# interface.net
KiCad netlist of a schematic drawn in Altium Designer
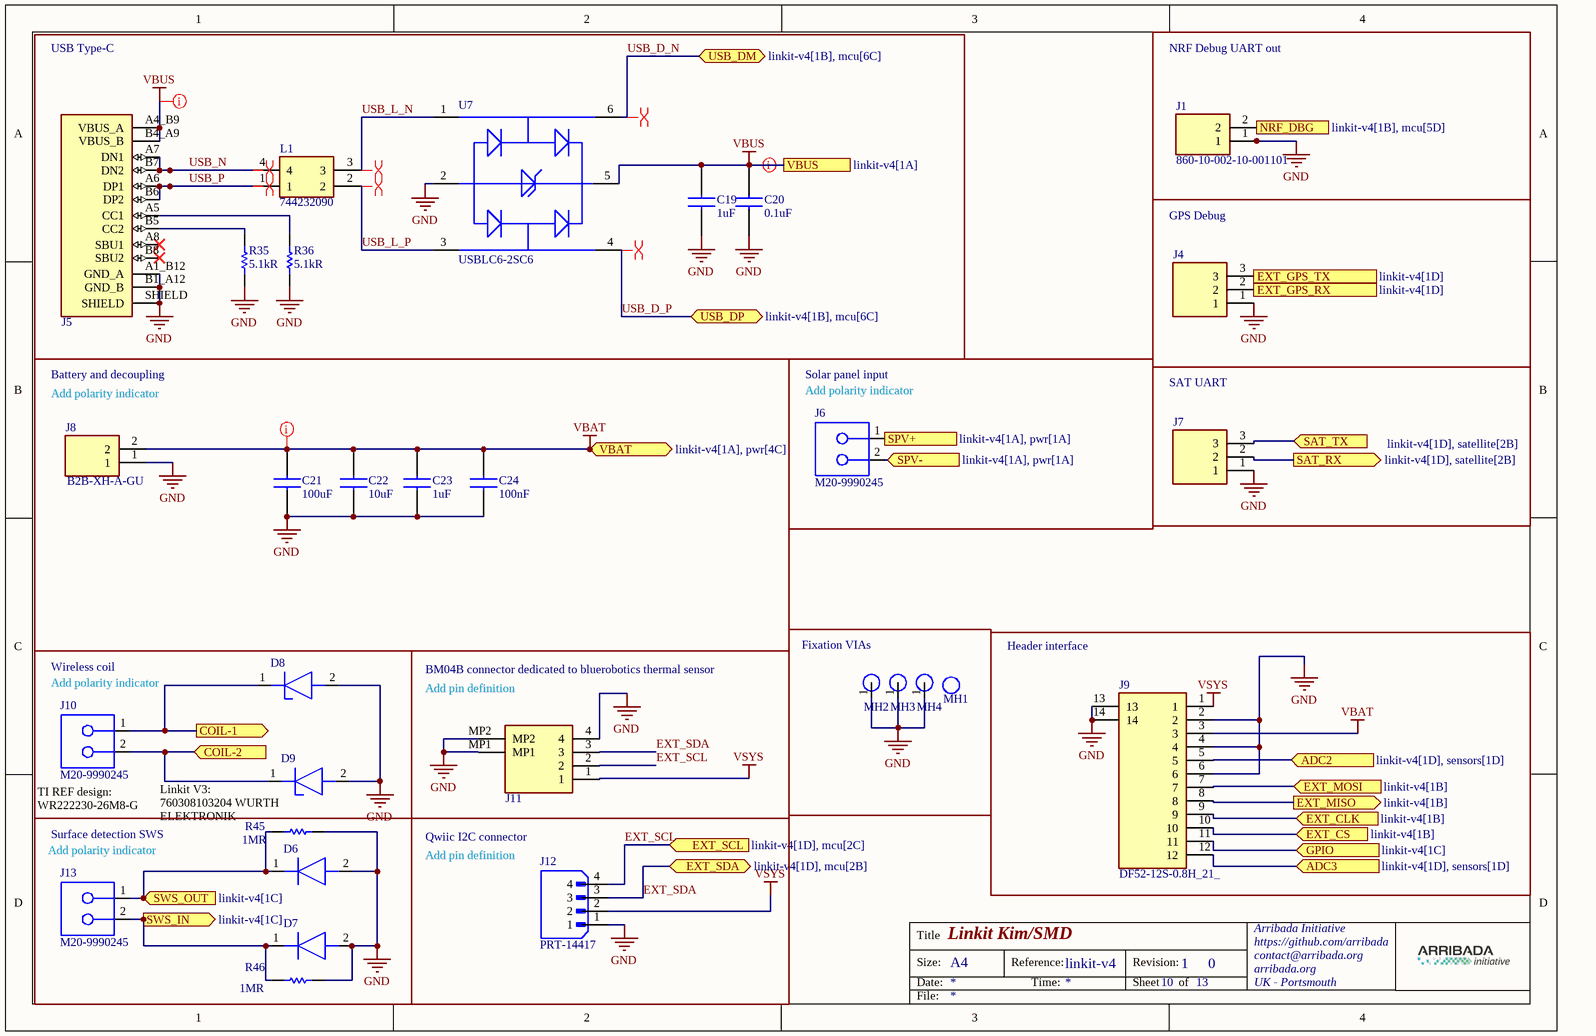
[diagram p0: interface.SchDoc]

(export (version "E")
  (design (tool "Eeschema 10.0.6"))
  (components
    (comp (ref "C19")
      (value "1uF")
      (footprint "CAPC0603X35N")
      (description "Multilayer Ceramic Capacitors MLCC - SMD/SMT 1uF+/-10% 10V X5R 06 0201")
      (fields
        (field (name "MOUSER PART NUMBER") "187-CL03A105KP3NSNC")
        (field (name "MANUFACTURER_PART_NUMBER") "CL03A105KP3NSNC")
      )
      (libsource (lib "stm32wl-dev") (part "CL03A105KP3NSNC"))
    )
    (comp (ref "C20")
      (value "0.1uF")
      (footprint "CAPC0603X33N")
      (description "Multilayer Ceramic Capacitors MLCC - SMD/SMT .1UF     16V   10%        0201")
      (fields
        (field (name "MOUSER PART NUMBER") "81-GRM033Z71C104KE4D")
        (field (name "MANUFACTURER_PART_NUMBER") "GRM033Z71C104KE14D")
      )
      (libsource (lib "stm32wl-dev") (part "GRM033Z71C104KE14D"))
    )
    (comp (ref "C21")
      (value "100uF")
      (footprint "CAPC3216X180N")
      (description "Multilayer Ceramic Capacitors MLCC - SMD/SMT 100 uF 10 VDC 20% 1206 X5R")
      (fields
        (field (name "MANUFACTURER_PART_NUMBER") "GRM31CR61A107MEA8L")
        (field (name "MOUSER PART NUMBER") "81-GRM31CR61A107MA8L")
      )
      (libsource (lib "stm32wl-dev") (part "GRM31CR61A107MEA8L"))
    )
    (comp (ref "C22")
      (value "10uF")
      (footprint "CAPC1005X55N")
      (description "Multilayer Ceramic Capacitors MLCC - SMD/SMT 10 uF 10 VDC 20% 0402 X5R")
      (fields
        (field (name "MANUFACTURER_PART_NUMBER") "GRM155R61A106ME11D")
        (field (name "MOUSER PART NUMBER") "81-GRM155R61A106ME1D")
      )
      (libsource (lib "stm32wl-dev") (part "GRM155R61A106ME11D"))
    )
    (comp (ref "C23")
      (value "1uF")
      (footprint "CAPC1005X55N")
      (description "Multilayer Ceramic Capacitors MLCC - SMD/SMT 1 uF 25 VDC 10% 0402 X5R")
      (fields
        (field (name "MANUFACTURER_PART_NUMBER") "GRM155R61E105KE11D")
        (field (name "MOUSER PART NUMBER") "81-GRM155R61E105KE1D")
      )
      (libsource (lib "stm32wl-dev") (part "GRM155R61E105KE11D"))
    )
    (comp (ref "C24")
      (value "100nF")
      (footprint "0402")
      (description "Multilayer Ceramic Capacitors MLCC - SMD/SMT 0.1 uF 16 VDC 10% 0402 X7R")
      (fields
        (field (name "MANUFACTURER_PART_NUMBER") "CC0402KRX7R7BB104")
        (field (name "MANUFACTURER") "YAGEO")
      )
      (libsource (lib "stm32wl-dev") (part "GRM155R71C104KA88D"))
    )
    (comp (ref "D6")
      (value "ESD9L5.0ST5GH")
      (footprint "stm32wl-dev:SODFL1006X40N")
      (description "Diode")
      (libsource (lib "*") (part "ESD9L5.0ST5GH"))
    )
    (comp (ref "D7")
      (value "ESD9L5.0ST5GH")
      (footprint "stm32wl-dev:SODFL1006X40N")
      (description "Diode")
      (libsource (lib "*") (part "ESD9L5.0ST5GH"))
    )
    (comp (ref "D8")
      (value "PESD12VS1UL,315")
      (footprint "stm32wl-dev:PESD5V0S1BL315")
      (description "Diode ESD (Uni-directional)")
      (fields (field (name "MOUSER PART NUMBER") "771-PESD12VS1UL315"))
      (libsource (lib "*") (part "PESD12VS1UL,315"))
    )
    (comp (ref "D9")
      (value "PESD12VS1UL,315")
      (footprint "stm32wl-dev:PESD5V0S1BL315")
      (description "Diode ESD (Uni-directional)")
      (fields (field (name "MOUSER PART NUMBER") "771-PESD12VS1UL315"))
      (libsource (lib "*") (part "PESD12VS1UL,315"))
    )
    (comp (ref "J1")
      (value "860-10-002-10-001101")
      (footprint "stm32wl-dev:8601000210001101")
      (description "Connector, Header 2 pos, 1 row, pitch 1mm")
      (fields (field (name "MOUSER PART NUMBER") "437-8601000210001101"))
      (libsource (lib "stm32wl-dev") (part "860-10-002-10-001101"))
    )
    (comp (ref "J4")
      (value "BC020-03-A-0200-0300-L-G")
      (footprint "stm32wl-dev:BC02003A02000300LG")
      (description "Connector")
      (libsource (lib "*") (part "BC020-03-A-0200-0300-L-G"))
    )
    (comp (ref "J5")
      (value "USB4215-03-A_REVA")
      (footprint "GCT_USB4215-03-A_REVA")
      (description "USB Connectors USB C Receptacle, Short Body, USB2.0, 16Pin, Horizontal, SMT")
      (fields (field (name "MF") "Global Connector Technology") (field (name "MP") "USB4215-03-A"))
      (libsource (lib "stm32wl-dev") (part "USB4215-03-A_REVA"))
    )
    (comp (ref "J6")
      (value "M20-9990245")
      (footprint "HDR 2POS 2.54MM THRU HOLE")
      (description "CON HDR 2POS HEADER 2.54MM VERT THRU HOLE")
      (fields (field (name "MANUFACTURER") "Harwin"))
      (libsource (lib "Connectors") (part "M20-9990245"))
    )
    (comp (ref "J7")
      (value "BC020-03-A-0200-0300-L-G")
      (footprint "stm32wl-dev:BC02003A02000300LG")
      (description "Connector")
      (libsource (lib "*") (part "BC020-03-A-0200-0300-L-G"))
    )
    (comp (ref "J8")
      (value "B2B-XH-A-GU")
      (footprint "stm32wl-dev:B2BXHAGU")
      (description "Connector")
      (libsource (lib "*") (part "B2B-XH-A-GU"))
    )
    (comp (ref "J9")
      (value "DF52-12S-0.8H_21_")
      (footprint "stm32wl-dev:DF5212S08H21")
      (description "Headers & Wire Housings Recep 12P R/A 0.8mm Pitch")
      (fields
        (field (name "MANUFACTURER_PART_NUMBER") "DF52-12S-0.8H(21)")
        (field (name "MOUSER PART NUMBER") "798-DF52-12S-0.8H21")
      )
      (libsource (lib "stm32wl-dev") (part "DF52-12S-0.8H_21_"))
    )
    (comp (ref "J10")
      (value "M20-9990245")
      (footprint "HDR 2POS 2.54MM THRU HOLE")
      (description "CON HDR 2POS HEADER 2.54MM VERT THRU HOLE")
      (fields (field (name "MANUFACTURER") "Harwin"))
      (libsource (lib "Connectors") (part "M20-9990245"))
    )
    (comp (ref "J11")
      (value "BM04B-GHS-TBT_LF__SN__N_")
      (footprint "CONN_BM04B-GHS-TBT_JST")
      (description "Headers & Wire Housings GH HEADER (SMT/TOP TYPE)")
      (fields (field (name "MANUFACTURER_PART_NUMBER") "BM04B-GHS-TBT(LF)(SN)(N)"))
      (libsource (lib "stm32wl-dev") (part "BM04B-GHS-TBT_LF__SN__N_"))
    )
    (comp (ref "J12")
      (value "PRT-14417")
      (footprint "SPARKFUN_PRT-14417")
      (description "QWIIC JST CONNECTOR - SMD 4-PIN")
      (fields (field (name "MF") "SparkFun Electronics"))
      (libsource (lib "stm32wl-dev") (part "PRT-14417"))
    )
    (comp (ref "J13")
      (value "M20-9990245")
      (footprint "HDR 2POS 2.54MM THRU HOLE")
      (description "CON HDR 2POS HEADER 2.54MM VERT THRU HOLE")
      (fields (field (name "MANUFACTURER") "Harwin"))
      (libsource (lib "Connectors") (part "M20-9990245"))
    )
    (comp (ref "L1")
      (value "744232090")
      (footprint "WE-CNSW-SMD")
      (description "Common Mode Chokes / Filters WE-CNSW 1206 370mA 90Ohm 100MHz AECQ200")
      (fields (field (name "MOUSER PART NUMBER") "710-744232090"))
      (libsource (lib "stm32wl-dev") (part "744232090"))
    )
    (comp (ref "MH1")
      (value "Mounting Hole M2")
      (footprint "MOUNTING HOLE M2 UNPLATED")
      (fields (field (name "MANUFACTURER") "NOT FITTED PART"))
      (libsource (lib "Misc") (part "Mounting Hole M2"))
    )
    (comp (ref "MH2")
      (value "Mounting Hole M2 Plated")
      (footprint "Mounting Hole M2 Plated")
      (fields (field (name "MANUFACTURER") "NOT FITTED PART"))
      (libsource (lib "Misc") (part "Mounting Hole M2 Plated"))
    )
    (comp (ref "MH3")
      (value "Mounting Hole M2 Plated")
      (footprint "Mounting Hole M2 Plated")
      (fields (field (name "MANUFACTURER") "NOT FITTED PART"))
      (libsource (lib "Misc") (part "Mounting Hole M2 Plated"))
    )
    (comp (ref "MH4")
      (value "Mounting Hole M2 Plated")
      (footprint "Mounting Hole M2 Plated")
      (fields (field (name "MANUFACTURER") "NOT FITTED PART"))
      (libsource (lib "Misc") (part "Mounting Hole M2 Plated"))
    )
    (comp (ref "R35")
      (value "5.1kR")
      (footprint "stm32wl-dev:RESC0603X28N")
      (description "Thick Film Resistors - SMD 1/20watt 5.1Kohms 5% 200ppm")
      (fields
        (field (name "MANUFACTURER_PART_NUMBER") "CRCW02015K10JNED")
        (field (name "MOUSER PART NUMBER") "71-CRCW02015K10JNED")
      )
      (libsource (lib "stm32wl-dev") (part "CRCW02015K10JNED"))
    )
    (comp (ref "R36")
      (value "5.1kR")
      (footprint "stm32wl-dev:RESC0603X28N")
      (description "Thick Film Resistors - SMD 1/20watt 5.1Kohms 5% 200ppm")
      (fields
        (field (name "MANUFACTURER_PART_NUMBER") "CRCW02015K10JNED")
        (field (name "MOUSER PART NUMBER") "71-CRCW02015K10JNED")
      )
      (libsource (lib "stm32wl-dev") (part "CRCW02015K10JNED"))
    )
    (comp (ref "R45")
      (value "1MR")
      (footprint "RESC0603X26N")
      (description "Thick Film Resistors - SMD 1 MOhms 50 mW 0201 1%")
      (fields
        (field (name "MANUFACTURER_PART_NUMBER") "RC0201FR-7D1ML")
        (field (name "MOUSER PART NUMBER") "603-RC0201FR-7D1ML")
      )
      (libsource (lib "stm32wl-dev") (part "RC0201FR-7D1ML"))
    )
    (comp (ref "R46")
      (value "1MR")
      (footprint "RESC0603X26N")
      (description "Thick Film Resistors - SMD 1 MOhms 50 mW 0201 1%")
      (fields
        (field (name "MANUFACTURER_PART_NUMBER") "RC0201FR-7D1ML")
        (field (name "MOUSER PART NUMBER") "603-RC0201FR-7D1ML")
      )
      (libsource (lib "stm32wl-dev") (part "RC0201FR-7D1ML"))
    )
    (comp (ref "U7")
      (value "USBLC6-2SC6")
      (footprint "stm32wl-dev:SOT95P280X145-6N")
      (description "ESD Suppressors / TVS Diodes High Speed Interface Protection Low Cap")
      (fields (field (name "MOUSER PART NUMBER") "511-USBLC6-2SC6"))
      (libsource (lib "stm32wl-dev") (part "USBLC6-2SC6"))
    )
  )
  (nets
    (net (code "1") (name "/ADC2") (class "Default")
      (node (ref "J9") (pin "5") (pinfunction "5_5") (pintype "passive"))
    )
    (net (code "2") (name "/ADC3") (class "Default")
      (node (ref "J9") (pin "12") (pinfunction "12_12") (pintype "passive"))
    )
    (net (code "3") (name "/COIL-1") (class "Default")
      (node (ref "D8") (pin "1") (pinfunction "K_1") (pintype "passive"))
      (node (ref "J10") (pin "1") (pinfunction "1_1") (pintype "passive"))
    )
    (net (code "4") (name "/COIL-2") (class "Default")
      (node (ref "D9") (pin "1") (pinfunction "K_1") (pintype "passive"))
      (node (ref "J10") (pin "2") (pinfunction "2_2") (pintype "passive"))
    )
    (net (code "5") (name "/EXT_CLK") (class "Default")
      (node (ref "J9") (pin "9") (pinfunction "9_9") (pintype "passive"))
    )
    (net (code "6") (name "/EXT_CS") (class "Default")
      (node (ref "J9") (pin "10") (pinfunction "10_10") (pintype "passive"))
    )
    (net (code "7") (name "/EXT_GPS_RX") (class "Default")
      (node (ref "J4") (pin "2") (pinfunction "2_2") (pintype "passive"))
    )
    (net (code "8") (name "/EXT_GPS_TX") (class "Default")
      (node (ref "J4") (pin "3") (pinfunction "3_3") (pintype "passive"))
    )
    (net (code "9") (name "/EXT_MISO") (class "Default")
      (node (ref "J9") (pin "8") (pinfunction "8_8") (pintype "passive"))
    )
    (net (code "10") (name "/EXT_MOSI") (class "Default")
      (node (ref "J9") (pin "7") (pinfunction "7_7") (pintype "passive"))
    )
    (net (code "11") (name "/EXT_SCL") (class "Default")
      (node (ref "J11") (pin "2") (pinfunction "2_2") (pintype "passive"))
      (node (ref "J12") (pin "4") (pinfunction "4_4") (pintype "passive"))
    )
    (net (code "12") (name "/EXT_SDA") (class "Default")
      (node (ref "J11") (pin "3") (pinfunction "3_3") (pintype "passive"))
      (node (ref "J12") (pin "3") (pinfunction "3_3") (pintype "passive"))
    )
    (net (code "13") (name "/GPIO") (class "Default")
      (node (ref "J9") (pin "11") (pinfunction "11_11") (pintype "passive"))
    )
    (net (code "14") (name "/NRF_DBG") (class "Default")
      (node (ref "J1") (pin "2") (pinfunction "2_2") (pintype "passive"))
    )
    (net (code "15") (name "/SAT_RX") (class "Default")
      (node (ref "J7") (pin "2") (pinfunction "2_2") (pintype "passive"))
    )
    (net (code "16") (name "/SAT_TX") (class "Default")
      (node (ref "J7") (pin "3") (pinfunction "3_3") (pintype "passive"))
    )
    (net (code "17") (name "/SPV+") (class "Default")
      (node (ref "J6") (pin "1") (pinfunction "1_1") (pintype "passive"))
    )
    (net (code "18") (name "/SPV-") (class "Default")
      (node (ref "J6") (pin "2") (pinfunction "2_2") (pintype "passive"))
    )
    (net (code "19") (name "/SWS_IN") (class "Default")
      (node (ref "D7") (pin "1") (pinfunction "K_1") (pintype "passive"))
      (node (ref "J13") (pin "2") (pinfunction "2_2") (pintype "passive"))
      (node (ref "R46") (pin "1") (pinfunction "1_1") (pintype "passive"))
    )
    (net (code "20") (name "/SWS_OUT") (class "Default")
      (node (ref "D6") (pin "1") (pinfunction "K_1") (pintype "passive"))
      (node (ref "J13") (pin "1") (pinfunction "1_1") (pintype "passive"))
      (node (ref "R45") (pin "1") (pinfunction "1_1") (pintype "passive"))
    )
    (net (code "21") (name "/USB_D_N") (class "Default")
      (node (ref "U7") (pin "6") (pinfunction "I/O1_2_6") (pintype "passive"))
    )
    (net (code "22") (name "/USB_D_P") (class "Default")
      (node (ref "U7") (pin "4") (pinfunction "I/O2_2_4") (pintype "passive"))
    )
    (net (code "23") (name "/USB_L_N") (class "Default")
      (node (ref "L1") (pin "3") (pinfunction "3_3") (pintype "passive"))
      (node (ref "U7") (pin "1") (pinfunction "I/O1_1_1") (pintype "passive"))
    )
    (net (code "24") (name "/USB_L_P") (class "Default")
      (node (ref "L1") (pin "2") (pinfunction "2_2") (pintype "passive"))
      (node (ref "U7") (pin "3") (pinfunction "I/O2_1_3") (pintype "passive"))
    )
    (net (code "25") (name "/USB_N") (class "Default")
      (node (ref "J5") (pin "A7") (pinfunction "DN1_A7") (pintype "bidirectional"))
      (node (ref "J5") (pin "B7") (pinfunction "DN2_B7") (pintype "bidirectional"))
      (node (ref "L1") (pin "4") (pinfunction "4_4") (pintype "passive"))
    )
    (net (code "26") (name "/USB_P") (class "Default")
      (node (ref "J5") (pin "A6") (pinfunction "DP1_A6") (pintype "bidirectional"))
      (node (ref "J5") (pin "B6") (pinfunction "DP2_B6") (pintype "bidirectional"))
      (node (ref "L1") (pin "1") (pinfunction "1_1") (pintype "passive"))
    )
    (net (code "27") (name "GND") (class "Default")
      (node (ref "C19") (pin "1") (pinfunction "1_1") (pintype "passive"))
      (node (ref "C20") (pin "1") (pinfunction "1_1") (pintype "passive"))
      (node (ref "C21") (pin "1") (pinfunction "1_1") (pintype "passive"))
      (node (ref "C22") (pin "2") (pinfunction "2_2") (pintype "passive"))
      (node (ref "C23") (pin "2") (pinfunction "2_2") (pintype "passive"))
      (node (ref "C24") (pin "2") (pinfunction "2_2") (pintype "passive"))
      (node (ref "D6") (pin "2") (pinfunction "A_2") (pintype "passive"))
      (node (ref "D7") (pin "2") (pinfunction "A_2") (pintype "passive"))
      (node (ref "D8") (pin "2") (pinfunction "A_2") (pintype "passive"))
      (node (ref "D9") (pin "2") (pinfunction "A_2") (pintype "passive"))
      (node (ref "J1") (pin "1") (pinfunction "1_1") (pintype "passive"))
      (node (ref "J11") (pin "4") (pinfunction "4_4") (pintype "passive"))
      (node (ref "J11") (pin "MP1") (pinfunction "MP1_MP1") (pintype "passive"))
      (node (ref "J11") (pin "MP2") (pinfunction "MP2_MP2") (pintype "passive"))
      (node (ref "J12") (pin "1") (pinfunction "1_1") (pintype "passive"))
      (node (ref "J4") (pin "1") (pinfunction "1_1") (pintype "passive"))
      (node (ref "J5") (pin "A1_B12") (pinfunction "GND_A_A1_B12") (pintype "power_in"))
      (node (ref "J5") (pin "B1_A12") (pinfunction "GND_B_B1_A12") (pintype "power_in"))
      (node (ref "J5") (pin "SHIELD") (pinfunction "SHIELD_SHIELD") (pintype "passive"))
      (node (ref "J7") (pin "1") (pinfunction "1_1") (pintype "passive"))
      (node (ref "J8") (pin "1") (pinfunction "1_1") (pintype "passive"))
      (node (ref "J9") (pin "13") (pinfunction "13_13") (pintype "passive"))
      (node (ref "J9") (pin "14") (pinfunction "14_14") (pintype "passive"))
      (node (ref "J9") (pin "2") (pinfunction "2_2") (pintype "passive"))
      (node (ref "J9") (pin "4") (pinfunction "4_4") (pintype "passive"))
      (node (ref "J9") (pin "6") (pinfunction "6_6") (pintype "passive"))
      (node (ref "MH2") (pin "1") (pinfunction "5_1") (pintype "passive"))
      (node (ref "MH3") (pin "1") (pinfunction "5_1") (pintype "passive"))
      (node (ref "MH4") (pin "1") (pinfunction "5_1") (pintype "passive"))
      (node (ref "R35") (pin "1") (pinfunction "1_1") (pintype "passive"))
      (node (ref "R36") (pin "1") (pinfunction "1_1") (pintype "passive"))
      (node (ref "R45") (pin "2") (pinfunction "2_2") (pintype "passive"))
      (node (ref "R46") (pin "2") (pinfunction "2_2") (pintype "passive"))
      (node (ref "U7") (pin "2") (pinfunction "GND_2") (pintype "passive"))
    )
    (net (code "28") (name "Net-(J5-CC1)") (class "Default")
      (node (ref "J5") (pin "A5") (pinfunction "CC1_A5") (pintype "bidirectional"))
      (node (ref "R36") (pin "2") (pinfunction "2_2") (pintype "passive"))
    )
    (net (code "29") (name "Net-(J5-CC2)") (class "Default")
      (node (ref "J5") (pin "B5") (pinfunction "CC2_B5") (pintype "bidirectional"))
      (node (ref "R35") (pin "2") (pinfunction "2_2") (pintype "passive"))
    )
    (net (code "30") (name "VBAT") (class "Default")
      (node (ref "C21") (pin "2") (pinfunction "2_2") (pintype "passive"))
      (node (ref "C22") (pin "1") (pinfunction "1_1") (pintype "passive"))
      (node (ref "C23") (pin "1") (pinfunction "1_1") (pintype "passive"))
      (node (ref "C24") (pin "1") (pinfunction "1_1") (pintype "passive"))
      (node (ref "J8") (pin "2") (pinfunction "2_2") (pintype "passive"))
      (node (ref "J9") (pin "3") (pinfunction "3_3") (pintype "passive"))
    )
    (net (code "31") (name "VBUS") (class "Default")
      (node (ref "C19") (pin "2") (pinfunction "2_2") (pintype "passive"))
      (node (ref "C20") (pin "2") (pinfunction "2_2") (pintype "passive"))
      (node (ref "J5") (pin "A4_B9") (pinfunction "VBUS_A_A4_B9") (pintype "power_in"))
      (node (ref "J5") (pin "B4_A9") (pinfunction "VBUS_B_B4_A9") (pintype "power_in"))
      (node (ref "U7") (pin "5") (pinfunction "VBUS_5") (pintype "passive"))
    )
    (net (code "32") (name "VSYS") (class "Default")
      (node (ref "J11") (pin "1") (pinfunction "1_1") (pintype "passive"))
      (node (ref "J12") (pin "2") (pinfunction "2_2") (pintype "passive"))
      (node (ref "J9") (pin "1") (pinfunction "1_1") (pintype "passive"))
    )
    (net (code "33") (name "unconnected-(J5-SBU1-PadA8)") (class "Default")
      (node (ref "J5") (pin "A8") (pinfunction "SBU1_A8") (pintype "bidirectional+no_connect"))
    )
    (net (code "34") (name "unconnected-(J5-SBU2-PadB8)") (class "Default")
      (node (ref "J5") (pin "B8") (pinfunction "SBU2_B8") (pintype "bidirectional+no_connect"))
    )
  )
)
